# power.net
KiCad netlist of a schematic drawn in Altium Designer
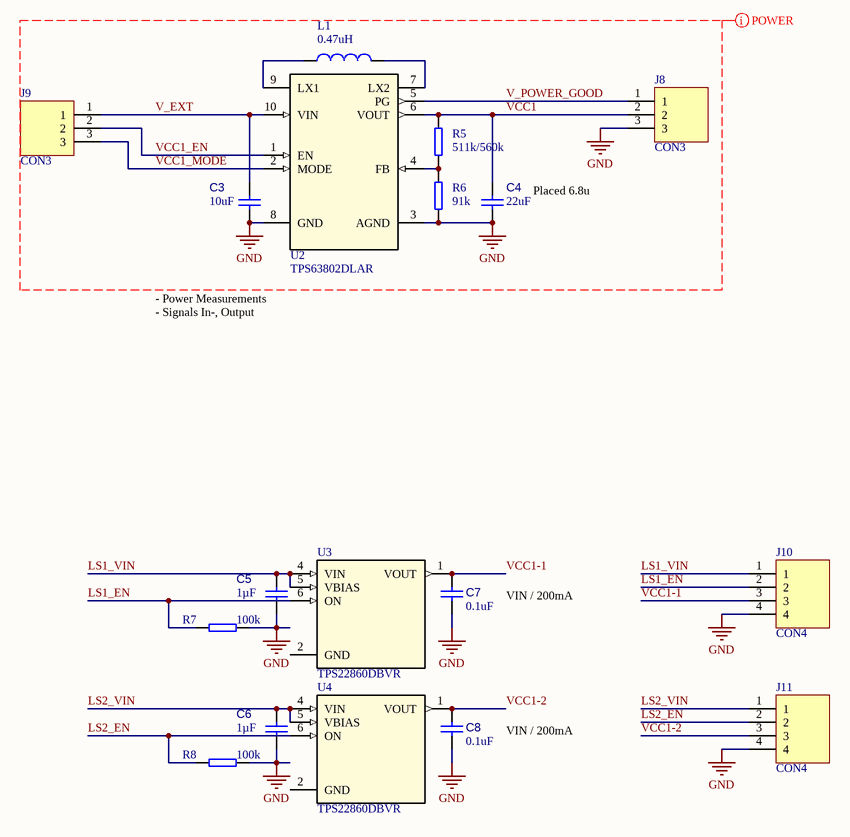
[diagram p0: power.SchDoc]

(export (version "E")
  (design (tool "Eeschema 10.0.6"))
  (components
    (comp (ref "C3")
      (value "10uF")
      (footprint "sensornode:0805_S")
      (description "Capacitor 0402")
      (fields (field (name "TOLERANCE") "10%") (field (name "MANUFACTURER") "TDK"))
      (libsource (lib "sensornode_v2") (part "C"))
    )
    (comp (ref "C4")
      (value "22uF")
      (footprint "sensornode:0805_S")
      (description "Capacitor 0402")
      (fields (field (name "TOLERANCE") "10%") (field (name "MANUFACTURER") "TDK"))
      (libsource (lib "sensornode_v2") (part "C"))
    )
    (comp (ref "C5")
      (value "1µF")
      (footprint "sensornode:0603")
      (description "Capacitor 0402")
      (fields (field (name "TOLERANCE") "10%") (field (name "MANUFACTURER") "TDK"))
      (libsource (lib "sensornode_v2") (part "C"))
    )
    (comp (ref "C6")
      (value "1µF")
      (footprint "sensornode:0603")
      (description "Capacitor 0402")
      (fields (field (name "TOLERANCE") "10%") (field (name "MANUFACTURER") "TDK"))
      (libsource (lib "sensornode_v2") (part "C"))
    )
    (comp (ref "C7")
      (value "0.1uF")
      (footprint "sensornode:0603")
      (description "Capacitor 0402")
      (fields (field (name "TOLERANCE") "10%") (field (name "MANUFACTURER") "TDK"))
      (libsource (lib "sensornode_v2") (part "C"))
    )
    (comp (ref "C8")
      (value "0.1uF")
      (footprint "sensornode:0603")
      (description "Capacitor 0402")
      (fields (field (name "TOLERANCE") "10%") (field (name "MANUFACTURER") "TDK"))
      (libsource (lib "sensornode_v2") (part "C"))
    )
    (comp (ref "J8")
      (value "CON3")
      (footprint "AMZ_Altium_Lib:HEADER_3_RM_2.54")
      (libsource (lib "AMZ_Altium_Lib") (part "CON3"))
    )
    (comp (ref "J9")
      (value "CON3")
      (footprint "AMZ_Altium_Lib:HEADER_3_RM_2.54")
      (libsource (lib "") (part "CON3_1"))
    )
    (comp (ref "J10")
      (value "CON4")
      (footprint "AMZ_Altium_Lib:HEADER_4_RM_2.54")
      (libsource (lib "AMZ_Altium_Lib") (part "CON4"))
    )
    (comp (ref "J11")
      (value "CON4")
      (footprint "AMZ_Altium_Lib:HEADER_4_RM_2.54")
      (libsource (lib "AMZ_Altium_Lib") (part "CON4"))
    )
    (comp (ref "L1")
      (value "0.47uH")
      (footprint "sensornode:1210")
      (libsource (lib "sensornode_v2") (part "L?"))
    )
    (comp (ref "R5")
      (value "511k/560k")
      (footprint "AMZ_Altium_Lib:0805_S")
      (description "Normaler Widerstand")
      (libsource (lib "sensornode_v2") (part "R?"))
    )
    (comp (ref "R6")
      (value "91k")
      (footprint "AMZ_Altium_Lib:0805_S")
      (description "Normaler Widerstand")
      (libsource (lib "sensornode_v2") (part "R?"))
    )
    (comp (ref "R7")
      (value "100k")
      (footprint "AMZ_Altium_Lib:0805")
      (description "Normaler Widerstand")
      (libsource (lib "sensornode_v2") (part "R?"))
    )
    (comp (ref "R8")
      (value "100k")
      (footprint "AMZ_Altium_Lib:0805")
      (description "Normaler Widerstand")
      (libsource (lib "sensornode_v2") (part "R?"))
    )
    (comp (ref "U2")
      (value "TPS63802DLAR")
      (footprint "sensornode:VREG_TPS63802DLAR")
      (fields (field (name "MF") "Richtek USA") (field (name "MP") "RT6150B-33GQW"))
      (libsource (lib "sensornode_v2") (part "TPS63802DLAR"))
    )
    (comp (ref "U3")
      (value "TPS22860DBVR")
      (footprint "sensornode:SOT95P280X145-6N")
      (description "0.73-?, 5-V, ultra-low leakage load switch 6-SOT-23 -40 to 85")
      (fields (field (name "MF") "Texas Instruments") (field (name "DIGI-KEY_PART_NUMBER") "296-43982-1-ND"))
      (libsource (lib "sensornode_v2") (part "TPS22860DBVR"))
    )
    (comp (ref "U4")
      (value "TPS22860DBVR")
      (footprint "sensornode:SOT95P280X145-6N")
      (description "0.73-?, 5-V, ultra-low leakage load switch 6-SOT-23 -40 to 85")
      (fields (field (name "MF") "Texas Instruments") (field (name "DIGI-KEY_PART_NUMBER") "296-43982-1-ND"))
      (libsource (lib "sensornode_v2") (part "TPS22860DBVR"))
    )
  )
  (nets
    (net (code "1") (name "/LS1_EN") (class "Default")
      (node (ref "J10") (pin "2") (pinfunction "2_2") (pintype "passive"))
      (node (ref "R7") (pin "1") (pintype "passive"))
      (node (ref "U3") (pin "6") (pinfunction "ON_6") (pintype "input"))
    )
    (net (code "2") (name "/LS1_VIN") (class "Default")
      (node (ref "C5") (pin "2") (pinfunction "2_2") (pintype "passive"))
      (node (ref "J10") (pin "1") (pinfunction "1_1") (pintype "passive"))
      (node (ref "U3") (pin "4") (pinfunction "VIN_4") (pintype "input"))
      (node (ref "U3") (pin "5") (pinfunction "VBIAS_5") (pintype "input"))
    )
    (net (code "3") (name "/LS2_EN") (class "Default")
      (node (ref "J11") (pin "2") (pinfunction "2_2") (pintype "passive"))
      (node (ref "R8") (pin "1") (pintype "passive"))
      (node (ref "U4") (pin "6") (pinfunction "ON_6") (pintype "input"))
    )
    (net (code "4") (name "/LS2_VIN") (class "Default")
      (node (ref "C6") (pin "2") (pinfunction "2_2") (pintype "passive"))
      (node (ref "J11") (pin "1") (pinfunction "1_1") (pintype "passive"))
      (node (ref "U4") (pin "4") (pinfunction "VIN_4") (pintype "input"))
      (node (ref "U4") (pin "5") (pinfunction "VBIAS_5") (pintype "input"))
    )
    (net (code "5") (name "/VCC1") (class "Default")
      (node (ref "C4") (pin "2") (pinfunction "2_2") (pintype "passive"))
      (node (ref "J8") (pin "2") (pinfunction "2_2") (pintype "passive"))
      (node (ref "R5") (pin "1") (pintype "passive"))
      (node (ref "U2") (pin "6") (pinfunction "VOUT_6") (pintype "output"))
    )
    (net (code "6") (name "/VCC1-1") (class "Default")
      (node (ref "C7") (pin "2") (pinfunction "2_2") (pintype "passive"))
      (node (ref "J10") (pin "3") (pinfunction "3_3") (pintype "passive"))
      (node (ref "U3") (pin "1") (pinfunction "VOUT_1") (pintype "output"))
    )
    (net (code "7") (name "/VCC1-2") (class "Default")
      (node (ref "C8") (pin "2") (pinfunction "2_2") (pintype "passive"))
      (node (ref "J11") (pin "3") (pinfunction "3_3") (pintype "passive"))
      (node (ref "U4") (pin "1") (pinfunction "VOUT_1") (pintype "output"))
    )
    (net (code "8") (name "/VCC1_EN") (class "Default")
      (node (ref "J9") (pin "2") (pinfunction "2_2") (pintype "passive"))
      (node (ref "U2") (pin "1") (pinfunction "EN_1") (pintype "input"))
    )
    (net (code "9") (name "/VCC1_MODE") (class "Default")
      (node (ref "J9") (pin "3") (pinfunction "3_3") (pintype "passive"))
      (node (ref "U2") (pin "2") (pinfunction "MODE_2") (pintype "input"))
    )
    (net (code "10") (name "/V_EXT") (class "Default")
      (node (ref "C3") (pin "2") (pinfunction "2_2") (pintype "passive"))
      (node (ref "J9") (pin "1") (pinfunction "1_1") (pintype "passive"))
      (node (ref "U2") (pin "10") (pinfunction "VIN_10") (pintype "input"))
    )
    (net (code "11") (name "/V_POWER_GOOD") (class "Default")
      (node (ref "J8") (pin "1") (pinfunction "1_1") (pintype "passive"))
      (node (ref "U2") (pin "5") (pinfunction "PG_5") (pintype "output"))
    )
    (net (code "12") (name "GND") (class "Default")
      (node (ref "C3") (pin "1") (pinfunction "1_1") (pintype "passive"))
      (node (ref "C4") (pin "1") (pinfunction "1_1") (pintype "passive"))
      (node (ref "C5") (pin "1") (pinfunction "1_1") (pintype "passive"))
      (node (ref "C6") (pin "1") (pinfunction "1_1") (pintype "passive"))
      (node (ref "C7") (pin "1") (pinfunction "1_1") (pintype "passive"))
      (node (ref "C8") (pin "1") (pinfunction "1_1") (pintype "passive"))
      (node (ref "J10") (pin "4") (pinfunction "4_4") (pintype "passive"))
      (node (ref "J11") (pin "4") (pinfunction "4_4") (pintype "passive"))
      (node (ref "J8") (pin "3") (pinfunction "3_3") (pintype "passive"))
      (node (ref "R6") (pin "2") (pintype "passive"))
      (node (ref "R7") (pin "2") (pintype "passive"))
      (node (ref "R8") (pin "2") (pintype "passive"))
      (node (ref "U2") (pin "3") (pinfunction "AGND_3") (pintype "power_in"))
      (node (ref "U2") (pin "8") (pinfunction "GND_8") (pintype "power_in"))
    )
    (net (code "13") (name "Net-(U2-FB)") (class "Default")
      (node (ref "R5") (pin "2") (pintype "passive"))
      (node (ref "R6") (pin "1") (pintype "passive"))
      (node (ref "U2") (pin "4") (pinfunction "FB_4") (pintype "input"))
    )
    (net (code "14") (name "Net-(U2-LX1)") (class "Default")
      (node (ref "L1") (pin "1") (pinfunction "1_1") (pintype "passive"))
      (node (ref "U2") (pin "9") (pinfunction "LX1_9") (pintype "passive"))
    )
    (net (code "15") (name "Net-(U2-LX2)") (class "Default")
      (node (ref "L1") (pin "2") (pinfunction "2_2") (pintype "passive"))
      (node (ref "U2") (pin "7") (pinfunction "LX2_7") (pintype "passive"))
    )
    (net (code "16") (name "unconnected-(U3-GND-Pad2)") (class "Default")
      (node (ref "U3") (pin "2") (pinfunction "GND_2") (pintype "power_in"))
    )
    (net (code "17") (name "unconnected-(U4-GND-Pad2)") (class "Default")
      (node (ref "U4") (pin "2") (pinfunction "GND_2") (pintype "power_in"))
    )
  )
)
